# minishield-springswitch.net
KiCad netlist of a schematic drawn in EAGLE
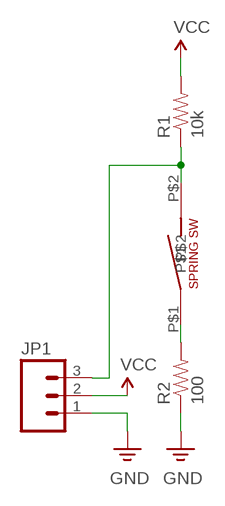
[diagram p0: schematic, sheet 1]

(export (version "E")
  (design (tool "Eeschema 10.0.6"))
  (components
    (comp (ref "JP1")
      (value "M03PTH")
      (footprint "eagle-import:1X03")
      (libsource (lib "eagle-import") (part "M03PTH"))
    )
    (comp (ref "R1")
      (value "10k")
      (footprint "eagle-import:0402-RES")
      (libsource (lib "eagle-import") (part "RESISTOR0402-RES"))
    )
    (comp (ref "R2")
      (value "100")
      (footprint "eagle-import:0402-RES")
      (libsource (lib "eagle-import") (part "RESISTOR0402-RES"))
    )
    (comp (ref "S1")
      (value "SPRING_SWITCH")
      (footprint "eagle-import:SW-18020P-RA")
      (libsource (lib "eagle-import") (part "SPRING_SWITCH"))
    )
  )
  (nets
    (net (code "1") (name "GND") (class "Default")
      (node (ref "JP1") (pin "1") (pinfunction "1_1") (pintype "passive"))
      (node (ref "R2") (pin "1") (pinfunction "1_1") (pintype "passive"))
    )
    (net (code "2") (name "Net-(JP1-Pad3)") (class "Default")
      (node (ref "JP1") (pin "3") (pinfunction "3_3") (pintype "passive"))
      (node (ref "R1") (pin "1") (pinfunction "1_1") (pintype "passive"))
      (node (ref "S1") (pin "P$2") (pinfunction "P$2_P$2") (pintype "bidirectional"))
    )
    (net (code "3") (name "Net-(R2-Pad2)") (class "Default")
      (node (ref "R2") (pin "2") (pinfunction "2_2") (pintype "passive"))
      (node (ref "S1") (pin "P$1") (pinfunction "P$1_P$1") (pintype "bidirectional"))
    )
    (net (code "4") (name "VCC") (class "Default")
      (node (ref "JP1") (pin "2") (pinfunction "2_2") (pintype "passive"))
      (node (ref "R1") (pin "2") (pinfunction "2_2") (pintype "passive"))
    )
  )
)
